# 1_Main.net
KiCad netlist of a schematic drawn in Altium Designer
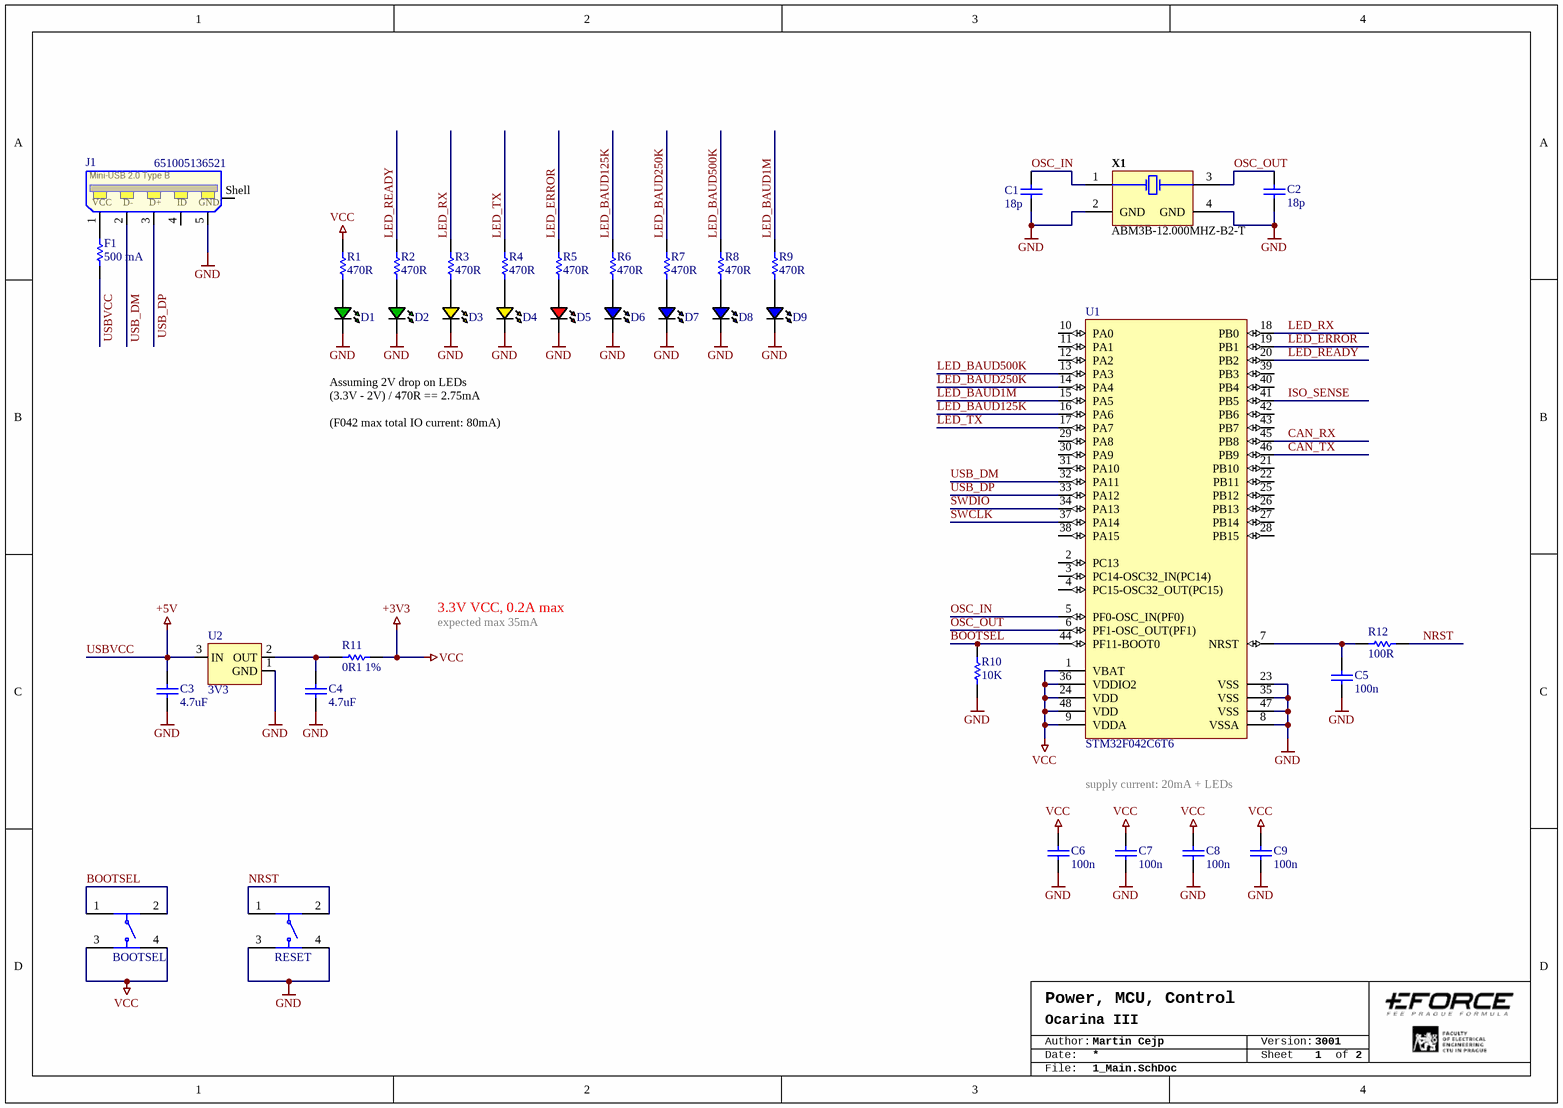
[diagram p0: 1_Main.SchDoc]

(export (version "E")
  (design (tool "Eeschema 10.0.6"))
  (components
    (comp (ref "BOOTSEL")
      (value "430181038816")
      (footprint "BUTTON_4x3x2")
      (description "WS-TASV 4.5x4.5 mm SMD")
      (fields (field (name "MANUFACTURER") "Wurth Elektronik") (field (name "CREATED BY") "Baojun Chen"))
      (libsource (lib "WS-TASV_rev15a") (part "WS-TASV, 430181038816"))
    )
    (comp (ref "C1")
      (value "18p")
      (footprint "CAPC0603(1608)100_M")
      (description "CAP 18pF 10V ±10% 0603 (1608 Metric) Thickness 1mm SMD")
      (fields (field (name "TOLERANCE") "Â±10%"))
      (libsource (lib "Altium Content Vault") (part "CAP"))
    )
    (comp (ref "C2")
      (value "18p")
      (footprint "CAPC0603(1608)100_M")
      (description "CAP 18pF 10V ±10% 0603 (1608 Metric) Thickness 1mm SMD")
      (fields (field (name "TOLERANCE") "Â±10%"))
      (libsource (lib "Altium Content Vault") (part "CAP"))
    )
    (comp (ref "C3")
      (value "4.7uF")
      (footprint "CAPC0805(2012)155_M")
      (description "CAP 4.7uF 16V ±20% 0805 (2012 Metric) Thickness 1.55mm SMD")
      (fields (field (name "TOLERANCE") "Â±20%"))
      (libsource (lib "Altium Content Vault") (part "CAP"))
    )
    (comp (ref "C4")
      (value "4.7uF")
      (footprint "CAPC0805(2012)155_M")
      (description "CAP 4.7uF 16V ±20% 0805 (2012 Metric) Thickness 1.55mm SMD")
      (fields (field (name "TOLERANCE") "Â±20%"))
      (libsource (lib "Altium Content Vault") (part "CAP"))
    )
    (comp (ref "C5")
      (value "100n")
      (footprint "CAPC0603(1608)100_M")
      (description "CAP 100nF 6.3V ±10% 0603 (1608 Metric) Thickness 1mm SMD")
      (fields (field (name "TOLERANCE") "Â±10%"))
      (libsource (lib "Altium Content Vault") (part "CAP"))
    )
    (comp (ref "C6")
      (value "100n")
      (footprint "CAPC0603(1608)100_M")
      (description "CAP 100nF 6.3V ±10% 0603 (1608 Metric) Thickness 1mm SMD")
      (fields (field (name "TOLERANCE") "Â±10%"))
      (libsource (lib "Altium Content Vault") (part "CAP"))
    )
    (comp (ref "C7")
      (value "100n")
      (footprint "CAPC0603(1608)100_M")
      (description "CAP 100nF 6.3V ±10% 0603 (1608 Metric) Thickness 1mm SMD")
      (fields (field (name "TOLERANCE") "Â±10%"))
      (libsource (lib "Altium Content Vault") (part "CAP"))
    )
    (comp (ref "C8")
      (value "100n")
      (footprint "CAPC0603(1608)100_M")
      (description "CAP 100nF 6.3V ±10% 0603 (1608 Metric) Thickness 1mm SMD")
      (fields (field (name "TOLERANCE") "Â±10%"))
      (libsource (lib "Altium Content Vault") (part "CAP"))
    )
    (comp (ref "C9")
      (value "100n")
      (footprint "CAPC0603(1608)100_M")
      (description "CAP 100nF 6.3V ±10% 0603 (1608 Metric) Thickness 1mm SMD")
      (fields (field (name "TOLERANCE") "Â±10%"))
      (libsource (lib "Altium Content Vault") (part "CAP"))
    )
    (comp (ref "D1")
      (value "green")
      (footprint "0805LEDG")
      (libsource (lib "eForce_-_Optical and Light") (part "LEDG_0805"))
    )
    (comp (ref "D2")
      (value "green")
      (footprint "0805LEDG")
      (libsource (lib "eForce_-_Optical and Light") (part "LEDG_0805"))
    )
    (comp (ref "D3")
      (value "yellow")
      (footprint "0805LEDYell")
      (libsource (lib "eForce_-_Optical and Light") (part "LEDYell_0805"))
    )
    (comp (ref "D4")
      (value "yellow")
      (footprint "0805LEDYell")
      (libsource (lib "eForce_-_Optical and Light") (part "LEDYell_0805"))
    )
    (comp (ref "D5")
      (value "red")
      (footprint "0805LEDR")
      (libsource (lib "eForce_-_Optical and Light") (part "LEDR_0805"))
    )
    (comp (ref "D6")
      (value "blue")
      (footprint "0805LEDB")
      (libsource (lib "eForce_-_Optical and Light") (part "LEDB_0805"))
    )
    (comp (ref "D7")
      (value "blue")
      (footprint "0805LEDB")
      (libsource (lib "eForce_-_Optical and Light") (part "LEDB_0805"))
    )
    (comp (ref "D8")
      (value "blue")
      (footprint "0805LEDB")
      (libsource (lib "eForce_-_Optical and Light") (part "LEDB_0805"))
    )
    (comp (ref "D9")
      (value "blue")
      (footprint "0805LEDB")
      (libsource (lib "eForce_-_Optical and Light") (part "LEDB_0805"))
    )
    (comp (ref "F1")
      (value "500 mA")
      (footprint "RESC1812(4532)_L")
      (description "1R02 0.75W 1% 1812 (4532 Metric)  SMD")
      (fields (field (name "POWER") "0.75 W") (field (name "TOLERANCE") "1 %"))
      (libsource (lib "Altium Content Vault") (part "RES"))
    )
    (comp (ref "J1")
      (value "651005136521")
      (footprint "MOLEX_548190519")
      (description "WR-COM Mini USB 2.0 Type B Horizontal 5 Contacts")
      (fields (field (name "PUBLISHER") "Wurth Elektronik"))
      (libsource (lib "ALTIUM-WR-COM-rev16d") (part "651005136521"))
    )
    (comp (ref "R1")
      (value "470R")
      (footprint "RESC0603(1608)_N")
      (description "470R 0.1W 5% 0603 (1608 Metric)  SMD")
      (fields (field (name "TOLERANCE") "5 %") (field (name "POWER") "0.1 W"))
      (libsource (lib "Altium Content Vault") (part "RES"))
    )
    (comp (ref "R2")
      (value "470R")
      (footprint "RESC0603(1608)_N")
      (description "470R 0.1W 5% 0603 (1608 Metric)  SMD")
      (fields (field (name "TOLERANCE") "5 %") (field (name "POWER") "0.1 W"))
      (libsource (lib "Altium Content Vault") (part "RES"))
    )
    (comp (ref "R3")
      (value "470R")
      (footprint "RESC0603(1608)_N")
      (description "470R 0.1W 5% 0603 (1608 Metric)  SMD")
      (fields (field (name "TOLERANCE") "5 %") (field (name "POWER") "0.1 W"))
      (libsource (lib "Altium Content Vault") (part "RES"))
    )
    (comp (ref "R4")
      (value "470R")
      (footprint "RESC0603(1608)_N")
      (description "470R 0.1W 5% 0603 (1608 Metric)  SMD")
      (fields (field (name "TOLERANCE") "5 %") (field (name "POWER") "0.1 W"))
      (libsource (lib "Altium Content Vault") (part "RES"))
    )
    (comp (ref "R5")
      (value "470R")
      (footprint "RESC0603(1608)_N")
      (description "470R 0.1W 5% 0603 (1608 Metric)  SMD")
      (fields (field (name "TOLERANCE") "5 %") (field (name "POWER") "0.1 W"))
      (libsource (lib "Altium Content Vault") (part "RES"))
    )
    (comp (ref "R6")
      (value "470R")
      (footprint "RESC0603(1608)_N")
      (description "470R 0.1W 5% 0603 (1608 Metric)  SMD")
      (fields (field (name "TOLERANCE") "5 %") (field (name "POWER") "0.1 W"))
      (libsource (lib "Altium Content Vault") (part "RES"))
    )
    (comp (ref "R7")
      (value "470R")
      (footprint "RESC0603(1608)_N")
      (description "470R 0.1W 5% 0603 (1608 Metric)  SMD")
      (fields (field (name "TOLERANCE") "5 %") (field (name "POWER") "0.1 W"))
      (libsource (lib "Altium Content Vault") (part "RES"))
    )
    (comp (ref "R8")
      (value "470R")
      (footprint "RESC0603(1608)_N")
      (description "470R 0.1W 5% 0603 (1608 Metric)  SMD")
      (fields (field (name "TOLERANCE") "5 %") (field (name "POWER") "0.1 W"))
      (libsource (lib "Altium Content Vault") (part "RES"))
    )
    (comp (ref "R9")
      (value "470R")
      (footprint "RESC0603(1608)_N")
      (description "470R 0.1W 5% 0603 (1608 Metric)  SMD")
      (fields (field (name "TOLERANCE") "5 %") (field (name "POWER") "0.1 W"))
      (libsource (lib "Altium Content Vault") (part "RES"))
    )
    (comp (ref "R10")
      (value "10K")
      (footprint "RESC0603(1608)_N")
      (description "10K 0.1W 5% 0603 (1608 Metric)  SMD")
      (fields (field (name "TOLERANCE") "5 %") (field (name "POWER") "0.1 W"))
      (libsource (lib "Altium Content Vault") (part "RES"))
    )
    (comp (ref "R11")
      (value "0R1 1%")
      (footprint "RESC1206(3216)_L")
      (description "0R1 0.25W 1% 1206 (3216 Metric)  SMD")
      (fields (field (name "POWER") "0.25 W") (field (name "TOLERANCE") "5 %"))
      (libsource (lib "Altium Content Vault") (part "CMP-1014-00003-1"))
    )
    (comp (ref "R12")
      (value "100R")
      (footprint "RESC0603(1608)_L")
      (description "100R 0.1W 5% 0603 (1608 Metric)  SMD")
      (fields (field (name "TOLERANCE") "5 %") (field (name "POWER") "0.1 W"))
      (libsource (lib "Altium Content Vault") (part "RES"))
    )
    (comp (ref "RESET")
      (value "430181038816")
      (footprint "BUTTON_4x3x2")
      (description "WS-TASV 4.5x4.5 mm SMD")
      (fields (field (name "MANUFACTURER") "Wurth Elektronik") (field (name "CREATED BY") "Baojun Chen"))
      (libsource (lib "WS-TASV_rev15a") (part "WS-TASV, 430181038816"))
    )
    (comp (ref "U1")
      (value "STM32F042C6T6")
      (footprint "STM-LQFP48_M")
      (libsource (lib "Altium Content Vault") (part "MC-ARM-STM32F042-LQFP48"))
    )
    (comp (ref "U2")
      (value "3V3")
      (footprint "SOT23m")
      (description "1.8V Voltage reference")
      (libsource (lib "eForce_-_Power Supplies") (part "LINREG_Vref_1V8"))
    )
    (comp (ref "X1")
      (value "ABM3B-12.000MHZ-B2-T")
      (footprint "ABRA-ABM3B-4_V")
      (description "Ceramic SMD Crystal, 12 MHz, +/- 20 ppm, 70 Ohm, -20 to 70 degC, 4-Pin SMD, RoHS, Tape and Reel")
      (libsource (lib "Altium Content Vault") (part "XTAL-1-3-4"))
    )
  )
  (nets
    (net (code "1") (name "+3V3") (class "Default")
      (node (ref "BOOTSEL") (pin "3") (pinfunction "3_3") (pintype "passive"))
      (node (ref "BOOTSEL") (pin "4") (pinfunction "4_4") (pintype "passive"))
      (node (ref "C6") (pin "1") (pinfunction "1_1") (pintype "passive"))
      (node (ref "C7") (pin "1") (pinfunction "1_1") (pintype "passive"))
      (node (ref "C8") (pin "1") (pinfunction "1_1") (pintype "passive"))
      (node (ref "C9") (pin "1") (pinfunction "1_1") (pintype "passive"))
      (node (ref "R1") (pin "2") (pinfunction "2_2") (pintype "passive"))
      (node (ref "R11") (pin "2") (pinfunction "2_2") (pintype "passive"))
      (node (ref "U1") (pin "1") (pinfunction "VBAT_1") (pintype "power_in"))
      (node (ref "U1") (pin "24") (pinfunction "VDD_24") (pintype "power_in"))
      (node (ref "U1") (pin "36") (pinfunction "VDDIO2_36") (pintype "power_in"))
      (node (ref "U1") (pin "48") (pinfunction "VDD_48") (pintype "power_in"))
      (node (ref "U1") (pin "9") (pinfunction "VDDA_9") (pintype "power_in"))
    )
    (net (code "2") (name "+5V") (class "Default")
      (node (ref "C3") (pin "2") (pinfunction "2_2") (pintype "passive"))
      (node (ref "F1") (pin "2") (pinfunction "2_2") (pintype "passive"))
      (node (ref "U2") (pin "3") (pinfunction "IN_3") (pintype "passive"))
    )
    (net (code "3") (name "/BOOTSEL") (class "Default")
      (node (ref "BOOTSEL") (pin "1") (pinfunction "1_1") (pintype "passive"))
      (node (ref "BOOTSEL") (pin "2") (pinfunction "2_2") (pintype "passive"))
      (node (ref "R10") (pin "2") (pinfunction "2_2") (pintype "passive"))
      (node (ref "U1") (pin "44") (pinfunction "PF11-BOOT0_44") (pintype "bidirectional"))
    )
    (net (code "4") (name "/CAN_RX") (class "Default")
      (node (ref "U1") (pin "45") (pinfunction "PB8_45") (pintype "bidirectional"))
    )
    (net (code "5") (name "/CAN_TX") (class "Default")
      (node (ref "U1") (pin "46") (pinfunction "PB9_46") (pintype "bidirectional"))
    )
    (net (code "6") (name "/ISO_SENSE") (class "Default")
      (node (ref "U1") (pin "41") (pinfunction "PB5_41") (pintype "bidirectional"))
    )
    (net (code "7") (name "/LED_BAUD1M") (class "Default")
      (node (ref "R9") (pin "1") (pinfunction "1_1") (pintype "passive"))
      (node (ref "U1") (pin "15") (pinfunction "PA5_15") (pintype "bidirectional"))
    )
    (net (code "8") (name "/LED_BAUD125K") (class "Default")
      (node (ref "R6") (pin "1") (pinfunction "1_1") (pintype "passive"))
      (node (ref "U1") (pin "16") (pinfunction "PA6_16") (pintype "bidirectional"))
    )
    (net (code "9") (name "/LED_BAUD250K") (class "Default")
      (node (ref "R7") (pin "1") (pinfunction "1_1") (pintype "passive"))
      (node (ref "U1") (pin "14") (pinfunction "PA4_14") (pintype "bidirectional"))
    )
    (net (code "10") (name "/LED_BAUD500K") (class "Default")
      (node (ref "R8") (pin "1") (pinfunction "1_1") (pintype "passive"))
      (node (ref "U1") (pin "13") (pinfunction "PA3_13") (pintype "bidirectional"))
    )
    (net (code "11") (name "/LED_ERROR") (class "Default")
      (node (ref "R5") (pin "1") (pinfunction "1_1") (pintype "passive"))
      (node (ref "U1") (pin "19") (pinfunction "PB1_19") (pintype "bidirectional"))
    )
    (net (code "12") (name "/LED_READY") (class "Default")
      (node (ref "R2") (pin "2") (pinfunction "2_2") (pintype "passive"))
      (node (ref "U1") (pin "20") (pinfunction "PB2_20") (pintype "bidirectional"))
    )
    (net (code "13") (name "/LED_RX") (class "Default")
      (node (ref "R3") (pin "1") (pinfunction "1_1") (pintype "passive"))
      (node (ref "U1") (pin "18") (pinfunction "PB0_18") (pintype "bidirectional"))
    )
    (net (code "14") (name "/LED_TX") (class "Default")
      (node (ref "R4") (pin "1") (pinfunction "1_1") (pintype "passive"))
      (node (ref "U1") (pin "17") (pinfunction "PA7_17") (pintype "bidirectional"))
    )
    (net (code "15") (name "/NRST") (class "Default")
      (node (ref "R12") (pin "2") (pinfunction "2_2") (pintype "passive"))
      (node (ref "RESET") (pin "1") (pinfunction "1_1") (pintype "passive"))
      (node (ref "RESET") (pin "2") (pinfunction "2_2") (pintype "passive"))
    )
    (net (code "16") (name "/OSC_IN") (class "Default")
      (node (ref "C1") (pin "2") (pinfunction "2_2") (pintype "passive"))
      (node (ref "U1") (pin "5") (pinfunction "PF0-OSC_IN(PF0)_5") (pintype "bidirectional"))
      (node (ref "X1") (pin "1") (pinfunction "X1_1") (pintype "passive"))
    )
    (net (code "17") (name "/OSC_OUT") (class "Default")
      (node (ref "C2") (pin "2") (pinfunction "2_2") (pintype "passive"))
      (node (ref "U1") (pin "6") (pinfunction "PF1-OSC_OUT(PF1)_6") (pintype "bidirectional"))
      (node (ref "X1") (pin "3") (pinfunction "X2_3") (pintype "passive"))
    )
    (net (code "18") (name "/SWCLK") (class "Default")
      (node (ref "U1") (pin "37") (pinfunction "PA14_37") (pintype "bidirectional"))
    )
    (net (code "19") (name "/SWDIO") (class "Default")
      (node (ref "U1") (pin "34") (pinfunction "PA13_34") (pintype "bidirectional"))
    )
    (net (code "20") (name "/USB_DM") (class "Default")
      (node (ref "J1") (pin "2") (pinfunction "D-_2") (pintype "passive"))
      (node (ref "U1") (pin "32") (pinfunction "PA11_32") (pintype "bidirectional"))
    )
    (net (code "21") (name "/USB_DP") (class "Default")
      (node (ref "J1") (pin "3") (pinfunction "D+_3") (pintype "passive"))
      (node (ref "U1") (pin "33") (pinfunction "PA12_33") (pintype "bidirectional"))
    )
    (net (code "22") (name "GND") (class "Default")
      (node (ref "C1") (pin "1") (pinfunction "1_1") (pintype "passive"))
      (node (ref "C2") (pin "1") (pinfunction "1_1") (pintype "passive"))
      (node (ref "C3") (pin "1") (pinfunction "1_1") (pintype "passive"))
      (node (ref "C4") (pin "1") (pinfunction "1_1") (pintype "passive"))
      (node (ref "C5") (pin "1") (pinfunction "1_1") (pintype "passive"))
      (node (ref "C6") (pin "2") (pinfunction "2_2") (pintype "passive"))
      (node (ref "C7") (pin "2") (pinfunction "2_2") (pintype "passive"))
      (node (ref "C8") (pin "2") (pinfunction "2_2") (pintype "passive"))
      (node (ref "C9") (pin "2") (pinfunction "2_2") (pintype "passive"))
      (node (ref "D1") (pin "K") (pinfunction "K_K") (pintype "passive"))
      (node (ref "D2") (pin "K") (pinfunction "K_K") (pintype "passive"))
      (node (ref "D3") (pin "K") (pinfunction "K_K") (pintype "passive"))
      (node (ref "D4") (pin "K") (pinfunction "K_K") (pintype "passive"))
      (node (ref "D5") (pin "K") (pinfunction "K_K") (pintype "passive"))
      (node (ref "D6") (pin "K") (pinfunction "K_K") (pintype "passive"))
      (node (ref "D7") (pin "K") (pinfunction "K_K") (pintype "passive"))
      (node (ref "D8") (pin "K") (pinfunction "K_K") (pintype "passive"))
      (node (ref "D9") (pin "K") (pinfunction "K_K") (pintype "passive"))
      (node (ref "J1") (pin "5") (pinfunction "GND_5") (pintype "passive"))
      (node (ref "R10") (pin "1") (pinfunction "1_1") (pintype "passive"))
      (node (ref "RESET") (pin "3") (pinfunction "3_3") (pintype "passive"))
      (node (ref "RESET") (pin "4") (pinfunction "4_4") (pintype "passive"))
      (node (ref "U1") (pin "23") (pinfunction "VSS_23") (pintype "power_in"))
      (node (ref "U1") (pin "35") (pinfunction "VSS_35") (pintype "power_in"))
      (node (ref "U1") (pin "47") (pinfunction "VSS_47") (pintype "power_in"))
      (node (ref "U1") (pin "8") (pinfunction "VSSA_8") (pintype "power_in"))
      (node (ref "U2") (pin "1") (pinfunction "GND_1") (pintype "passive"))
      (node (ref "X1") (pin "2") (pinfunction "GND_2") (pintype "power_in"))
      (node (ref "X1") (pin "4") (pinfunction "GND_4") (pintype "power_in"))
    )
    (net (code "23") (name "Net-(D1-PadA)") (class "Default")
      (node (ref "D1") (pin "A") (pinfunction "A_A") (pintype "passive"))
      (node (ref "R1") (pin "1") (pinfunction "1_1") (pintype "passive"))
    )
    (net (code "24") (name "Net-(D2-PadA)") (class "Default")
      (node (ref "D2") (pin "A") (pinfunction "A_A") (pintype "passive"))
      (node (ref "R2") (pin "1") (pinfunction "1_1") (pintype "passive"))
    )
    (net (code "25") (name "Net-(D3-PadA)") (class "Default")
      (node (ref "D3") (pin "A") (pinfunction "A_A") (pintype "passive"))
      (node (ref "R3") (pin "2") (pinfunction "2_2") (pintype "passive"))
    )
    (net (code "26") (name "Net-(D4-PadA)") (class "Default")
      (node (ref "D4") (pin "A") (pinfunction "A_A") (pintype "passive"))
      (node (ref "R4") (pin "2") (pinfunction "2_2") (pintype "passive"))
    )
    (net (code "27") (name "Net-(D5-PadA)") (class "Default")
      (node (ref "D5") (pin "A") (pinfunction "A_A") (pintype "passive"))
      (node (ref "R5") (pin "2") (pinfunction "2_2") (pintype "passive"))
    )
    (net (code "28") (name "Net-(D6-PadA)") (class "Default")
      (node (ref "D6") (pin "A") (pinfunction "A_A") (pintype "passive"))
      (node (ref "R6") (pin "2") (pinfunction "2_2") (pintype "passive"))
    )
    (net (code "29") (name "Net-(D7-PadA)") (class "Default")
      (node (ref "D7") (pin "A") (pinfunction "A_A") (pintype "passive"))
      (node (ref "R7") (pin "2") (pinfunction "2_2") (pintype "passive"))
    )
    (net (code "30") (name "Net-(D8-PadA)") (class "Default")
      (node (ref "D8") (pin "A") (pinfunction "A_A") (pintype "passive"))
      (node (ref "R8") (pin "2") (pinfunction "2_2") (pintype "passive"))
    )
    (net (code "31") (name "Net-(D9-PadA)") (class "Default")
      (node (ref "D9") (pin "A") (pinfunction "A_A") (pintype "passive"))
      (node (ref "R9") (pin "2") (pinfunction "2_2") (pintype "passive"))
    )
    (net (code "32") (name "Net-(J1-VCC)") (class "Default")
      (node (ref "F1") (pin "1") (pinfunction "1_1") (pintype "passive"))
      (node (ref "J1") (pin "1") (pinfunction "VCC_1") (pintype "passive"))
    )
    (net (code "33") (name "Net-(U1-NRST)") (class "Default")
      (node (ref "C5") (pin "2") (pinfunction "2_2") (pintype "passive"))
      (node (ref "R12") (pin "1") (pinfunction "1_1") (pintype "passive"))
      (node (ref "U1") (pin "7") (pinfunction "NRST_7") (pintype "bidirectional"))
    )
    (net (code "34") (name "Net-(U2-OUT)") (class "Default")
      (node (ref "C4") (pin "2") (pinfunction "2_2") (pintype "passive"))
      (node (ref "R11") (pin "1") (pinfunction "1_1") (pintype "passive"))
      (node (ref "U2") (pin "2") (pinfunction "OUT_2") (pintype "passive"))
    )
    (net (code "35") (name "unconnected-(J1-ID-Pad4)") (class "Default")
      (node (ref "J1") (pin "4") (pinfunction "ID_4") (pintype "passive"))
    )
    (net (code "36") (name "unconnected-(J1-PadShell)") (class "Default")
      (node (ref "J1") (pin "Shell") (pinfunction "Shell_Shell") (pintype "passive"))
    )
    (net (code "37") (name "unconnected-(U1-PA0-Pad10)") (class "Default")
      (node (ref "U1") (pin "10") (pinfunction "PA0_10") (pintype "bidirectional"))
    )
    (net (code "38") (name "unconnected-(U1-PA1-Pad11)") (class "Default")
      (node (ref "U1") (pin "11") (pinfunction "PA1_11") (pintype "bidirectional"))
    )
    (net (code "39") (name "unconnected-(U1-PA2-Pad12)") (class "Default")
      (node (ref "U1") (pin "12") (pinfunction "PA2_12") (pintype "bidirectional"))
    )
    (net (code "40") (name "unconnected-(U1-PA8-Pad29)") (class "Default")
      (node (ref "U1") (pin "29") (pinfunction "PA8_29") (pintype "bidirectional"))
    )
    (net (code "41") (name "unconnected-(U1-PA9-Pad30)") (class "Default")
      (node (ref "U1") (pin "30") (pinfunction "PA9_30") (pintype "bidirectional"))
    )
    (net (code "42") (name "unconnected-(U1-PA10-Pad31)") (class "Default")
      (node (ref "U1") (pin "31") (pinfunction "PA10_31") (pintype "bidirectional"))
    )
    (net (code "43") (name "unconnected-(U1-PA15-Pad38)") (class "Default")
      (node (ref "U1") (pin "38") (pinfunction "PA15_38") (pintype "bidirectional"))
    )
    (net (code "44") (name "unconnected-(U1-PB3-Pad39)") (class "Default")
      (node (ref "U1") (pin "39") (pinfunction "PB3_39") (pintype "bidirectional"))
    )
    (net (code "45") (name "unconnected-(U1-PB4-Pad40)") (class "Default")
      (node (ref "U1") (pin "40") (pinfunction "PB4_40") (pintype "bidirectional"))
    )
    (net (code "46") (name "unconnected-(U1-PB6-Pad42)") (class "Default")
      (node (ref "U1") (pin "42") (pinfunction "PB6_42") (pintype "bidirectional"))
    )
    (net (code "47") (name "unconnected-(U1-PB7-Pad43)") (class "Default")
      (node (ref "U1") (pin "43") (pinfunction "PB7_43") (pintype "bidirectional"))
    )
    (net (code "48") (name "unconnected-(U1-PB10-Pad21)") (class "Default")
      (node (ref "U1") (pin "21") (pinfunction "PB10_21") (pintype "bidirectional"))
    )
    (net (code "49") (name "unconnected-(U1-PB11-Pad22)") (class "Default")
      (node (ref "U1") (pin "22") (pinfunction "PB11_22") (pintype "bidirectional"))
    )
    (net (code "50") (name "unconnected-(U1-PB12-Pad25)") (class "Default")
      (node (ref "U1") (pin "25") (pinfunction "PB12_25") (pintype "bidirectional"))
    )
    (net (code "51") (name "unconnected-(U1-PB13-Pad26)") (class "Default")
      (node (ref "U1") (pin "26") (pinfunction "PB13_26") (pintype "bidirectional"))
    )
    (net (code "52") (name "unconnected-(U1-PB14-Pad27)") (class "Default")
      (node (ref "U1") (pin "27") (pinfunction "PB14_27") (pintype "bidirectional"))
    )
    (net (code "53") (name "unconnected-(U1-PB15-Pad28)") (class "Default")
      (node (ref "U1") (pin "28") (pinfunction "PB15_28") (pintype "bidirectional"))
    )
    (net (code "54") (name "unconnected-(U1-PC13-Pad2)") (class "Default")
      (node (ref "U1") (pin "2") (pinfunction "PC13_2") (pintype "bidirectional"))
    )
    (net (code "55") (name "unconnected-(U1-PC14-OSC32_IN(PC14)-Pad3)") (class "Default")
      (node (ref "U1") (pin "3") (pinfunction "PC14-OSC32_IN(PC14)_3") (pintype "bidirectional"))
    )
    (net (code "56") (name "unconnected-(U1-PC15-OSC32_OUT(PC15)-Pad4)") (class "Default")
      (node (ref "U1") (pin "4") (pinfunction "PC15-OSC32_OUT(PC15)_4") (pintype "bidirectional"))
    )
  )
)
